# SHIELD2.net
KiCad netlist of a schematic drawn in Altium Designer
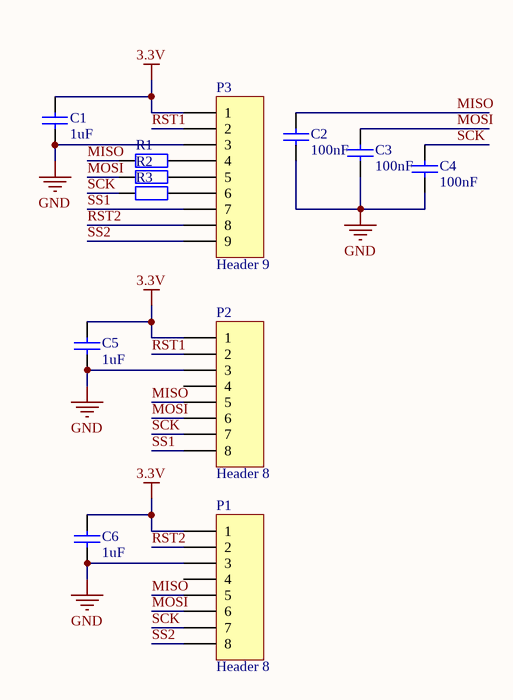
[diagram p0: SHIELD2.SchDoc]

(export (version "E")
  (design (tool "Eeschema 10.0.6"))
  (components
    (comp (ref "C1")
      (value "1uF")
      (footprint "C0805")
      (description "Capacitor")
      (fields (field (name "Comment") "Cap") (field (name "PUBLISHER") "Altium Limited"))
      (libsource (lib "Library") (part "Cap"))
    )
    (comp (ref "C2")
      (value "100nF")
      (footprint "C0805")
      (description "Capacitor")
      (fields (field (name "Comment") "Cap") (field (name "PUBLISHER") "Altium Limited"))
      (libsource (lib "Library") (part "Cap"))
    )
    (comp (ref "C3")
      (value "100nF")
      (footprint "C0805")
      (description "Capacitor")
      (fields (field (name "Comment") "Cap") (field (name "PUBLISHER") "Altium Limited"))
      (libsource (lib "Library") (part "Cap"))
    )
    (comp (ref "C4")
      (value "100nF")
      (footprint "C0805")
      (description "Capacitor")
      (fields (field (name "Comment") "Cap") (field (name "PUBLISHER") "Altium Limited"))
      (libsource (lib "Library") (part "Cap"))
    )
    (comp (ref "C5")
      (value "1uF")
      (footprint "C0805")
      (description "Capacitor")
      (fields (field (name "Comment") "Cap") (field (name "PUBLISHER") "Altium Limited"))
      (libsource (lib "Library") (part "Cap"))
    )
    (comp (ref "C6")
      (value "1uF")
      (footprint "C0805")
      (description "Capacitor")
      (fields (field (name "Comment") "Cap") (field (name "PUBLISHER") "Altium Limited"))
      (libsource (lib "Library") (part "Cap"))
    )
    (comp (ref "P1")
      (value "Header 8")
      (footprint "HDR1X8")
      (description "Header, 8-Pin")
      (fields (field (name "PUBLISHER") "Altium Limited"))
      (libsource (lib "Miscellaneous Connectors") (part "Header 8"))
    )
    (comp (ref "P2")
      (value "Header 8")
      (footprint "HDR1X8")
      (description "Header, 8-Pin")
      (fields (field (name "PUBLISHER") "Altium Limited"))
      (libsource (lib "Miscellaneous Connectors") (part "Header 8"))
    )
    (comp (ref "P3")
      (value "Header 9")
      (footprint "HDR1X9")
      (description "Header, 9-Pin")
      (fields (field (name "PUBLISHER") "Altium Limited"))
      (libsource (lib "Miscellaneous Connectors") (part "Header 9"))
    )
    (comp (ref "R1")
      (value "Res2")
      (footprint "6-0805_N")
      (description "Resistor")
      (fields (field (name "PUBLISHER") "Altium Limited"))
      (libsource (lib "Library") (part "Res2"))
    )
    (comp (ref "R2")
      (value "Res2")
      (footprint "6-0805_N")
      (description "Resistor")
      (fields (field (name "PUBLISHER") "Altium Limited"))
      (libsource (lib "Library") (part "Res2"))
    )
    (comp (ref "R3")
      (value "Res2")
      (footprint "6-0805_N")
      (description "Resistor")
      (fields (field (name "PUBLISHER") "Altium Limited"))
      (libsource (lib "Library") (part "Res2"))
    )
  )
  (nets
    (net (code "1") (name "/MISO") (class "Default")
      (node (ref "C2") (pin "2") (pinfunction "2_2") (pintype "passive"))
      (node (ref "P1") (pin "5") (pinfunction "5_5") (pintype "passive"))
      (node (ref "P2") (pin "5") (pinfunction "5_5") (pintype "passive"))
      (node (ref "R1") (pin "1") (pinfunction "1_1") (pintype "passive"))
    )
    (net (code "2") (name "/MOSI") (class "Default")
      (node (ref "C3") (pin "1") (pinfunction "1_1") (pintype "passive"))
      (node (ref "P1") (pin "6") (pinfunction "6_6") (pintype "passive"))
      (node (ref "P2") (pin "6") (pinfunction "6_6") (pintype "passive"))
      (node (ref "R2") (pin "1") (pinfunction "1_1") (pintype "passive"))
    )
    (net (code "3") (name "/RST1") (class "Default")
      (node (ref "P2") (pin "2") (pinfunction "2_2") (pintype "passive"))
      (node (ref "P3") (pin "2") (pinfunction "2_2") (pintype "passive"))
    )
    (net (code "4") (name "/RST2") (class "Default")
      (node (ref "P1") (pin "2") (pinfunction "2_2") (pintype "passive"))
      (node (ref "P3") (pin "8") (pinfunction "8_8") (pintype "passive"))
    )
    (net (code "5") (name "/SCK") (class "Default")
      (node (ref "C4") (pin "1") (pinfunction "1_1") (pintype "passive"))
      (node (ref "P1") (pin "7") (pinfunction "7_7") (pintype "passive"))
      (node (ref "P2") (pin "7") (pinfunction "7_7") (pintype "passive"))
      (node (ref "R3") (pin "1") (pinfunction "1_1") (pintype "passive"))
    )
    (net (code "6") (name "/SS1") (class "Default")
      (node (ref "P2") (pin "8") (pinfunction "8_8") (pintype "passive"))
      (node (ref "P3") (pin "7") (pinfunction "7_7") (pintype "passive"))
    )
    (net (code "7") (name "/SS2") (class "Default")
      (node (ref "P1") (pin "8") (pinfunction "8_8") (pintype "passive"))
      (node (ref "P3") (pin "9") (pinfunction "9_9") (pintype "passive"))
    )
    (net (code "8") (name "3.3V") (class "Default")
      (node (ref "C1") (pin "2") (pinfunction "2_2") (pintype "passive"))
      (node (ref "C5") (pin "2") (pinfunction "2_2") (pintype "passive"))
      (node (ref "C6") (pin "2") (pinfunction "2_2") (pintype "passive"))
      (node (ref "P1") (pin "1") (pinfunction "1_1") (pintype "passive"))
      (node (ref "P2") (pin "1") (pinfunction "1_1") (pintype "passive"))
      (node (ref "P3") (pin "1") (pinfunction "1_1") (pintype "passive"))
    )
    (net (code "9") (name "GND") (class "Default")
      (node (ref "C1") (pin "1") (pinfunction "1_1") (pintype "passive"))
      (node (ref "C2") (pin "1") (pinfunction "1_1") (pintype "passive"))
      (node (ref "C3") (pin "2") (pinfunction "2_2") (pintype "passive"))
      (node (ref "C4") (pin "2") (pinfunction "2_2") (pintype "passive"))
      (node (ref "C5") (pin "1") (pinfunction "1_1") (pintype "passive"))
      (node (ref "C6") (pin "1") (pinfunction "1_1") (pintype "passive"))
      (node (ref "P1") (pin "3") (pinfunction "3_3") (pintype "passive"))
      (node (ref "P2") (pin "3") (pinfunction "3_3") (pintype "passive"))
      (node (ref "P3") (pin "3") (pinfunction "3_3") (pintype "passive"))
    )
    (net (code "10") (name "Net-(P3-Pad4)") (class "Default")
      (node (ref "P3") (pin "4") (pinfunction "4_4") (pintype "passive"))
      (node (ref "R1") (pin "2") (pinfunction "2_2") (pintype "passive"))
    )
    (net (code "11") (name "Net-(P3-Pad5)") (class "Default")
      (node (ref "P3") (pin "5") (pinfunction "5_5") (pintype "passive"))
      (node (ref "R2") (pin "2") (pinfunction "2_2") (pintype "passive"))
    )
    (net (code "12") (name "Net-(P3-Pad6)") (class "Default")
      (node (ref "P3") (pin "6") (pinfunction "6_6") (pintype "passive"))
      (node (ref "R3") (pin "2") (pinfunction "2_2") (pintype "passive"))
    )
    (net (code "13") (name "unconnected-(P1-Pad4)") (class "Default")
      (node (ref "P1") (pin "4") (pinfunction "4_4") (pintype "passive"))
    )
    (net (code "14") (name "unconnected-(P2-Pad4)") (class "Default")
      (node (ref "P2") (pin "4") (pinfunction "4_4") (pintype "passive"))
    )
  )
)
